# PowerDistribution2022.net
KiCad netlist of a schematic drawn in EAGLE
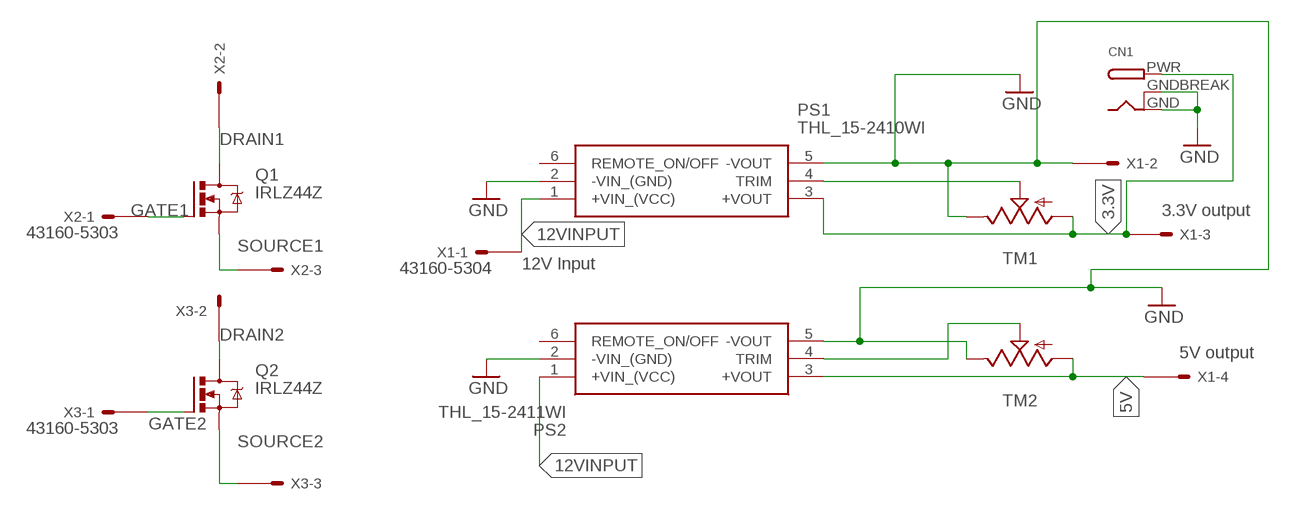
[diagram p0: schematic, sheet 1]

(export (version "E")
  (design (tool "Eeschema 10.0.6"))
  (components
    (comp (ref "CN1")
      (value "DCBARRELPTH")
      (footprint "eagle-import:DCJACK_2MM_PTH")
      (libsource (lib "eagle-import") (part "DCBARRELPTH"))
    )
    (comp (ref "PS1")
      (value "THL_15-2410WI")
      (footprint "eagle-import:THL152410WI")
      (fields
        (field (name "MANUFACTURER_PART_NUMBER") "THL 15-2410WI")
        (field (name "MOUSER_PART_NUMBER") "495-THL15-2410WI")
      )
      (libsource (lib "eagle-import") (part "THL_15-2410WI"))
    )
    (comp (ref "PS2")
      (value "THL_15-2411WI")
      (footprint "eagle-import:THL152411WI")
      (fields
        (field (name "MANUFACTURER_PART_NUMBER") "THL 15-2411WI")
        (field (name "MOUSER_PART_NUMBER") "495-THL15-2411WI")
      )
      (libsource (lib "eagle-import") (part "THL_15-2411WI"))
    )
    (comp (ref "Q1")
      (value "IRLZ44Z")
      (footprint "eagle-import:TO220BH")
      (fields (field (name "MF") "Infineon Technologies"))
      (libsource (lib "eagle-import") (part "IRLZ44Z"))
    )
    (comp (ref "Q2")
      (value "IRLZ44Z")
      (footprint "eagle-import:TO220BH")
      (fields (field (name "MF") "Infineon Technologies"))
      (libsource (lib "eagle-import") (part "IRLZ44Z"))
    )
    (comp (ref "TM1")
      (value "TRIM")
      (footprint "eagle-import:6MM")
      (libsource (lib "eagle-import") (part "TRIM"))
    )
    (comp (ref "TM2")
      (value "TRIM")
      (footprint "eagle-import:6MM")
      (libsource (lib "eagle-import") (part "TRIM"))
    )
    (comp (ref "X1")
      (value "43160-5304")
      (footprint "eagle-import:43160-XX04")
      (fields (field (name "MF") "MOLEX"))
      (libsource (lib "eagle-import") (part "43160-0453"))
    )
    (comp (ref "X2")
      (value "43160-5303")
      (footprint "eagle-import:43160-XX03")
      (fields (field (name "MF") "MOLEX"))
      (libsource (lib "eagle-import") (part "43160-0353"))
    )
    (comp (ref "X3")
      (value "43160-5303")
      (footprint "eagle-import:43160-XX03")
      (fields (field (name "MF") "MOLEX"))
      (libsource (lib "eagle-import") (part "43160-0353"))
    )
  )
  (nets
    (net (code "1") (name "/DRAIN1") (class "Default")
      (node (ref "Q1") (pin "D") (pinfunction "D_D") (pintype "passive"))
      (node (ref "X2") (pin "2@1") (pinfunction "S_2@1") (pintype "passive"))
    )
    (net (code "2") (name "/DRAIN2") (class "Default")
      (node (ref "Q2") (pin "D") (pinfunction "D_D") (pintype "passive"))
      (node (ref "X3") (pin "2@1") (pinfunction "S_2@1") (pintype "passive"))
    )
    (net (code "3") (name "/GATE1") (class "Default")
      (node (ref "Q1") (pin "G") (pinfunction "G_G") (pintype "passive"))
      (node (ref "X2") (pin "1@1") (pinfunction "S_1@1") (pintype "passive"))
    )
    (net (code "4") (name "/GATE2") (class "Default")
      (node (ref "Q2") (pin "G") (pinfunction "G_G") (pintype "passive"))
      (node (ref "X3") (pin "1@1") (pinfunction "S_1@1") (pintype "passive"))
    )
    (net (code "5") (name "/SOURCE1") (class "Default")
      (node (ref "Q1") (pin "S") (pinfunction "S_S") (pintype "passive"))
      (node (ref "X2") (pin "3@1") (pinfunction "S_3@1") (pintype "passive"))
    )
    (net (code "6") (name "/SOURCE2") (class "Default")
      (node (ref "Q2") (pin "S") (pinfunction "S_S") (pintype "passive"))
      (node (ref "X3") (pin "3@1") (pinfunction "S_3@1") (pintype "passive"))
    )
    (net (code "7") (name "3.3V") (class "Default")
      (node (ref "CN1") (pin "PWR") (pinfunction "PWR_PWR") (pintype "power_in"))
      (node (ref "PS1") (pin "3") (pinfunction "+VOUT_3") (pintype "bidirectional"))
      (node (ref "TM1") (pin "A") (pinfunction "A_A") (pintype "passive"))
      (node (ref "X1") (pin "3@1") (pinfunction "S_3@1") (pintype "passive"))
    )
    (net (code "8") (name "5V") (class "Default")
      (node (ref "PS2") (pin "3") (pinfunction "+VOUT_3") (pintype "bidirectional"))
      (node (ref "TM2") (pin "A") (pinfunction "A_A") (pintype "passive"))
      (node (ref "X1") (pin "4@1") (pinfunction "S_4@1") (pintype "passive"))
    )
    (net (code "9") (name "12VINPUT") (class "Default")
      (node (ref "PS1") (pin "1") (pinfunction "+VIN_(VCC)_1") (pintype "bidirectional"))
      (node (ref "PS2") (pin "1") (pinfunction "+VIN_(VCC)_1") (pintype "bidirectional"))
      (node (ref "X1") (pin "1@1") (pinfunction "S_1@1") (pintype "passive"))
    )
    (net (code "10") (name "GND") (class "Default")
      (node (ref "CN1") (pin "GND") (pinfunction "GND_GND") (pintype "power_in"))
      (node (ref "CN1") (pin "GNDBREAK") (pinfunction "GNDBREAK_GNDBREAK") (pintype "power_in"))
      (node (ref "PS1") (pin "2") (pinfunction "-VIN_(GND)_2") (pintype "bidirectional"))
      (node (ref "PS1") (pin "5") (pinfunction "-VOUT_5") (pintype "bidirectional"))
      (node (ref "PS2") (pin "2") (pinfunction "-VIN_(GND)_2") (pintype "bidirectional"))
      (node (ref "PS2") (pin "5") (pinfunction "-VOUT_5") (pintype "bidirectional"))
      (node (ref "TM1") (pin "E") (pinfunction "E_E") (pintype "passive"))
      (node (ref "TM2") (pin "E") (pinfunction "E_E") (pintype "passive"))
      (node (ref "X1") (pin "2@1") (pinfunction "S_2@1") (pintype "passive"))
    )
    (net (code "11") (name "Net-(PS1-TRIM)") (class "Default")
      (node (ref "PS1") (pin "4") (pinfunction "TRIM_4") (pintype "bidirectional"))
      (node (ref "TM1") (pin "S") (pinfunction "S_S") (pintype "passive"))
    )
    (net (code "12") (name "Net-(PS2-TRIM)") (class "Default")
      (node (ref "PS2") (pin "4") (pinfunction "TRIM_4") (pintype "bidirectional"))
      (node (ref "TM2") (pin "S") (pinfunction "S_S") (pintype "passive"))
    )
    (net (code "13") (name "unconnected-(PS1-REMOTE_ON{slash}OFF-Pad6)") (class "Default")
      (node (ref "PS1") (pin "6") (pinfunction "REMOTE_ON/OFF_6") (pintype "bidirectional"))
    )
    (net (code "14") (name "unconnected-(PS2-REMOTE_ON{slash}OFF-Pad6)") (class "Default")
      (node (ref "PS2") (pin "6") (pinfunction "REMOTE_ON/OFF_6") (pintype "bidirectional"))
    )
    (net (code "15") (name "unconnected-(X1A-S-Pad1@2)") (class "Default")
      (node (ref "X1") (pin "1@2") (pinfunction "S_1@2") (pintype "passive"))
    )
    (net (code "16") (name "unconnected-(X1B-S-Pad2@2)") (class "Default")
      (node (ref "X1") (pin "2@2") (pinfunction "S_2@2") (pintype "passive"))
    )
    (net (code "17") (name "unconnected-(X1C-S-Pad3@2)") (class "Default")
      (node (ref "X1") (pin "3@2") (pinfunction "S_3@2") (pintype "passive"))
    )
    (net (code "18") (name "unconnected-(X1D-S-Pad4@2)") (class "Default")
      (node (ref "X1") (pin "4@2") (pinfunction "S_4@2") (pintype "passive"))
    )
    (net (code "19") (name "unconnected-(X2A-S-Pad1@2)") (class "Default")
      (node (ref "X2") (pin "1@2") (pinfunction "S_1@2") (pintype "passive"))
    )
    (net (code "20") (name "unconnected-(X2B-S-Pad2@2)") (class "Default")
      (node (ref "X2") (pin "2@2") (pinfunction "S_2@2") (pintype "passive"))
    )
    (net (code "21") (name "unconnected-(X2C-S-Pad3@2)") (class "Default")
      (node (ref "X2") (pin "3@2") (pinfunction "S_3@2") (pintype "passive"))
    )
    (net (code "22") (name "unconnected-(X3A-S-Pad1@2)") (class "Default")
      (node (ref "X3") (pin "1@2") (pinfunction "S_1@2") (pintype "passive"))
    )
    (net (code "23") (name "unconnected-(X3B-S-Pad2@2)") (class "Default")
      (node (ref "X3") (pin "2@2") (pinfunction "S_2@2") (pintype "passive"))
    )
    (net (code "24") (name "unconnected-(X3C-S-Pad3@2)") (class "Default")
      (node (ref "X3") (pin "3@2") (pinfunction "S_3@2") (pintype "passive"))
    )
  )
)
